# SCH_prosthetic_2026-05-21.net
KiCad netlist of a schematic drawn in EasyEDA
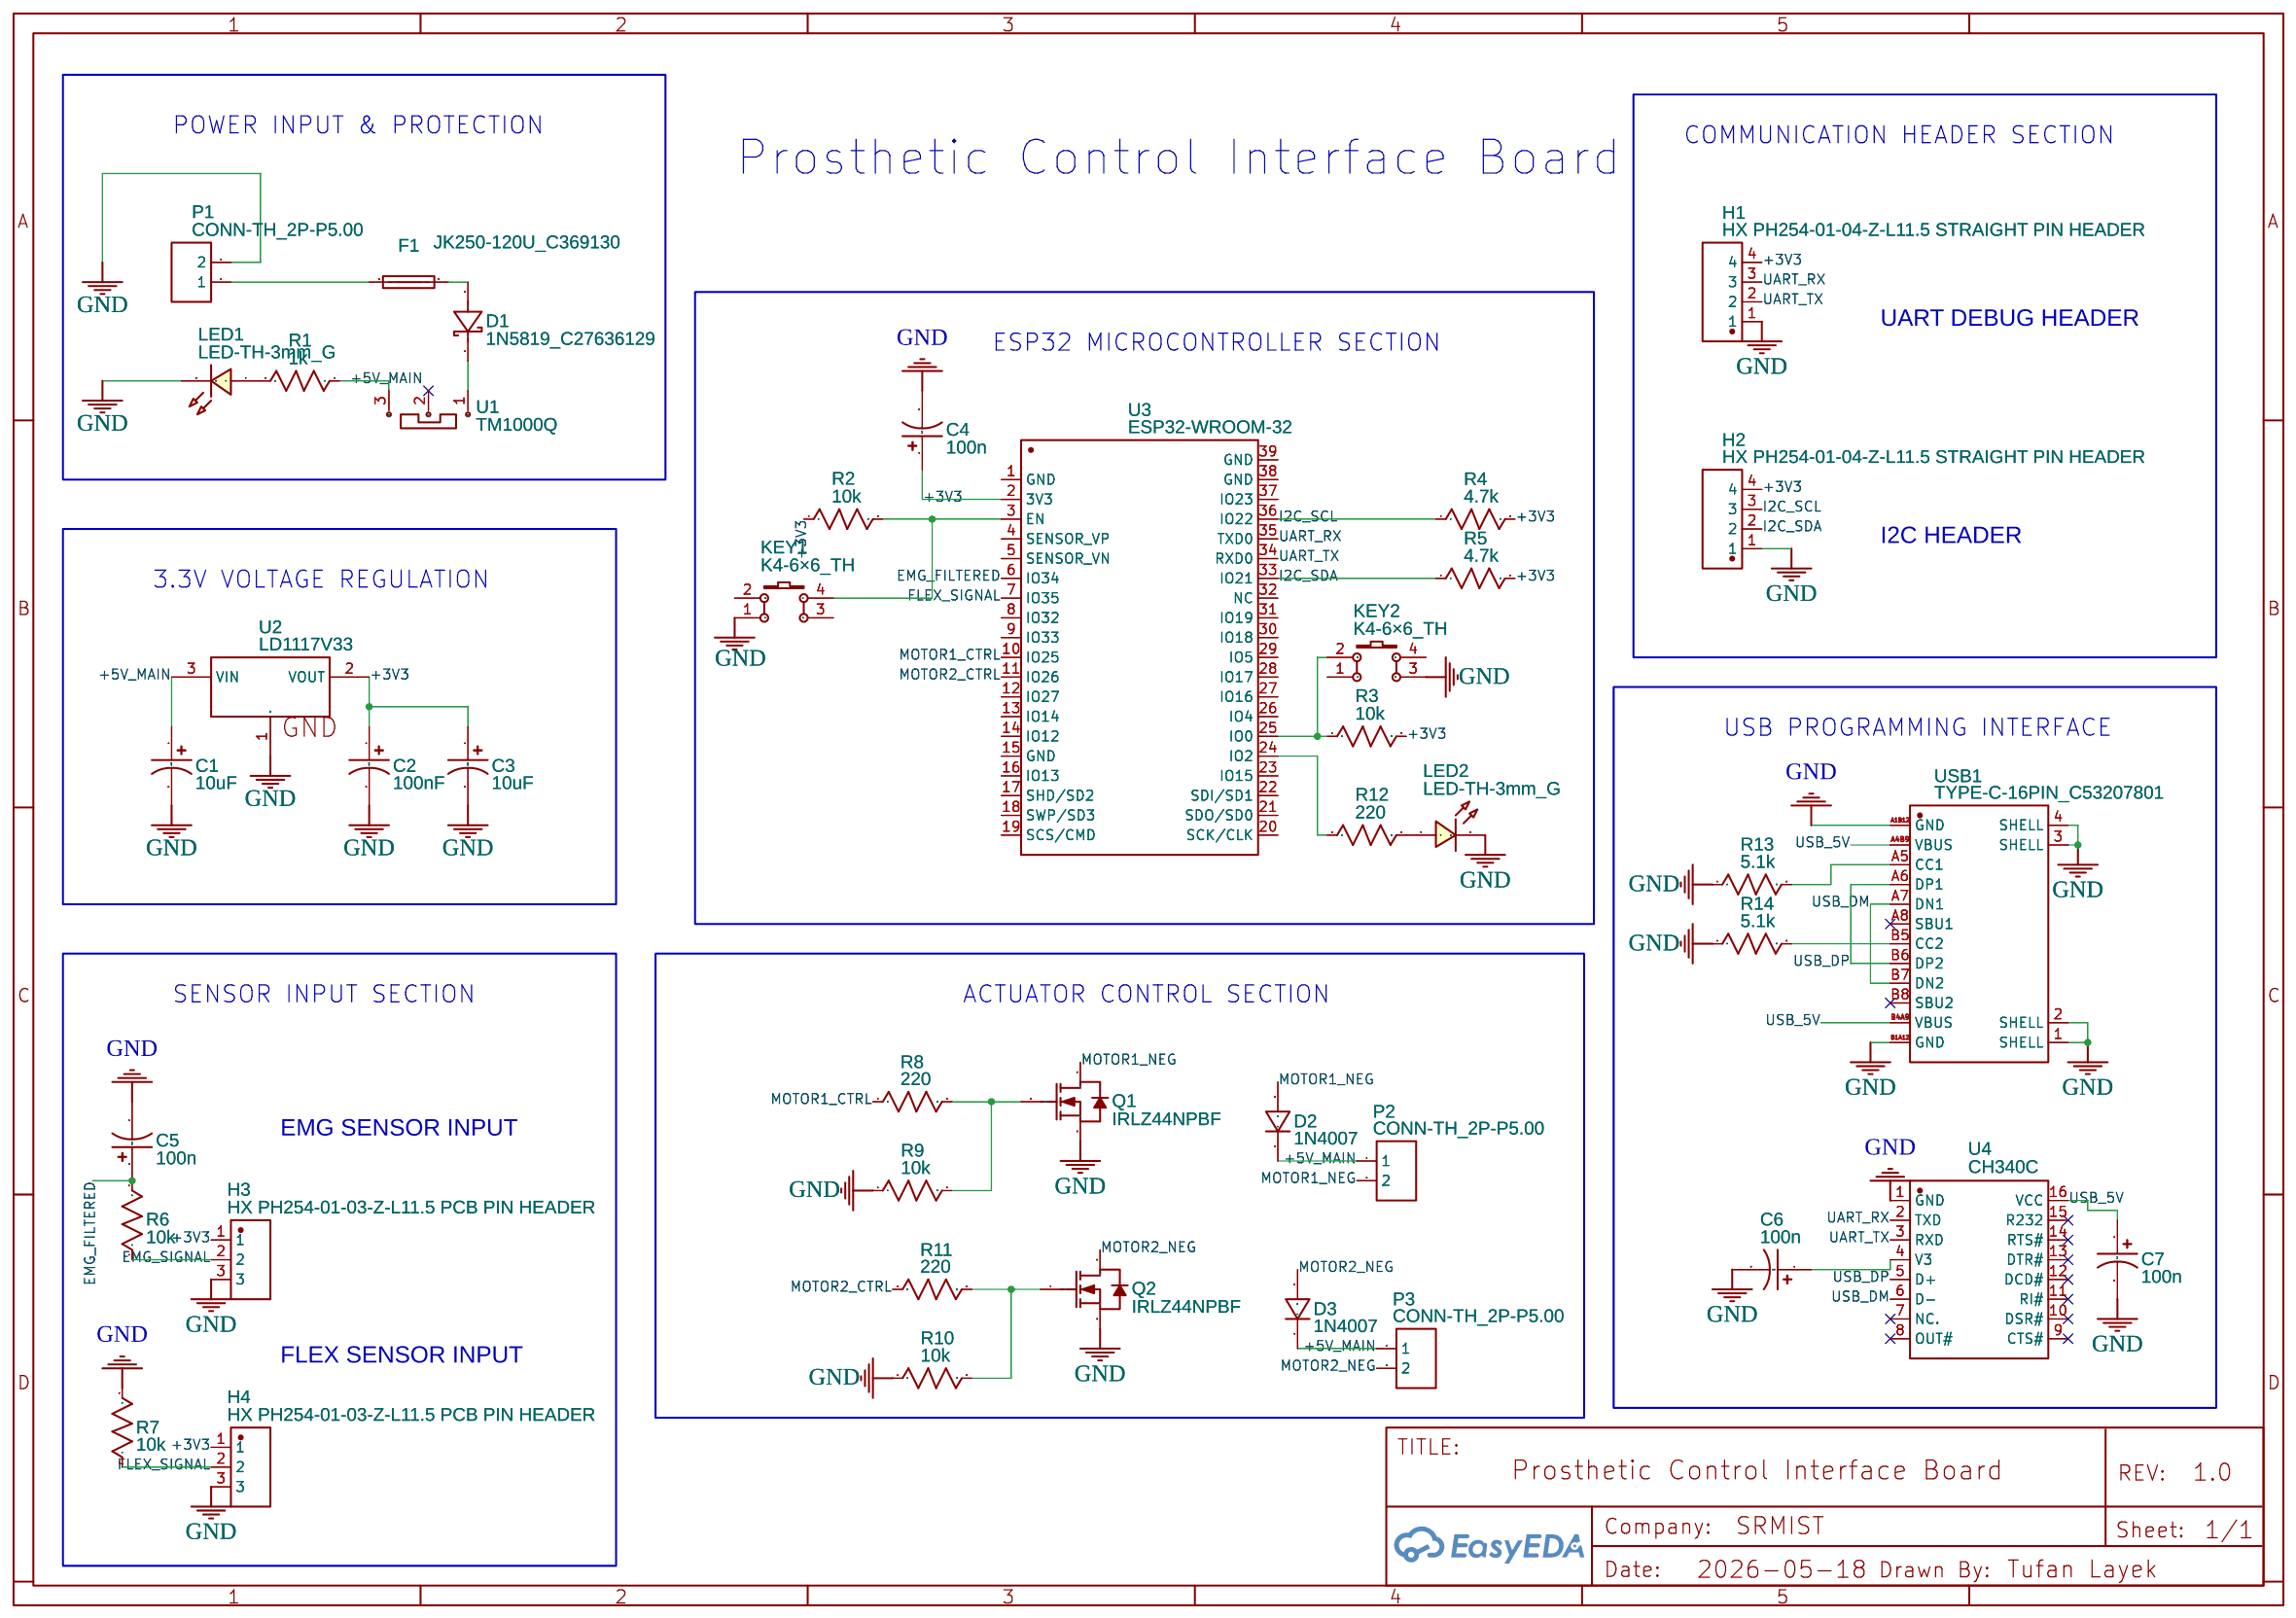
[diagram p0: schematic sheet]

(export (version "E")
  (design (tool "Eeschema 10.0.6"))
  (components
    (comp (ref "C1")
      (value "10uF")
      (fields (field (name "Manufacturer Part") "10UF50VC110GL") (field (name "Manufacturer") "Econd(米朗电子)"))
      (libsource (lib "") (part "CE_TH_D4.0×F1.5_US_2"))
    )
    (comp (ref "C2")
      (value "100nF")
      (fields
        (field (name "Manufacturer Part") "B220630V104J7ABLBY")
        (field (name "Manufacturer") "QIXING(七星)")
      )
      (libsource (lib "") (part "CE_TH_D4.0×F1.5_US_2"))
    )
    (comp (ref "C3")
      (value "10uF")
      (fields (field (name "Manufacturer Part") "10UF50VC110GL") (field (name "Manufacturer") "Econd(米朗电子)"))
      (libsource (lib "") (part "CE_TH_D4.0×F1.5_US_2"))
    )
    (comp (ref "C4")
      (value "100n")
      (fields (field (name "Manufacturer Part") "I104K44LEXLX") (field (name "Manufacturer") "CKX(錞谷)"))
      (libsource (lib "") (part "CE_TH_D4.0×F1.5_US_1"))
    )
    (comp (ref "C5")
      (value "100n")
      (fields (field (name "Manufacturer Part") "I104K44LEXLX") (field (name "Manufacturer") "CKX(錞谷)"))
      (libsource (lib "") (part "CE_TH_D4.0×F1.5_US_4"))
    )
    (comp (ref "C6")
      (value "100n")
      (fields (field (name "Manufacturer Part") "I104K44LEXLX") (field (name "Manufacturer") "CKX(錞谷)"))
      (libsource (lib "") (part "CE_TH_D4.0×F1.5_US"))
    )
    (comp (ref "C7")
      (value "100n")
      (fields (field (name "Manufacturer Part") "I104K44LEXLX") (field (name "Manufacturer") "CKX(錞谷)"))
      (libsource (lib "") (part "CE_TH_D4.0×F1.5_US_3"))
    )
    (comp (ref "D1")
      (value "1N5819_C27636129")
      (fields (field (name "Manufacturer Part") "1N5819") (field (name "Manufacturer") "DOWO(东沃)"))
      (libsource (lib "") (part "1N5819_C27636129"))
    )
    (comp (ref "D2")
      (value "1N4007")
      (fields (field (name "Manufacturer") "SEMTECH"))
      (libsource (lib "") (part "1N4007"))
    )
    (comp (ref "D3")
      (value "1N4007")
      (fields (field (name "Manufacturer") "SEMTECH"))
      (libsource (lib "") (part "1N4007"))
    )
    (comp (ref "F1")
      (value "JK250-120U_C369130")
      (fields (field (name "Manufacturer Part") "JK250-120U") (field (name "Manufacturer") "JK(金科)"))
      (libsource (lib "") (part "JK250-120U_C369130"))
    )
    (comp (ref "H1")
      (value "HX PH254-01-04-Z-L11.5 STRAIGHT PIN HEADER")
      (fields
        (field (name "Manufacturer Part") "HX PH254-01-04-Z-L11.5 straight pin header")
        (field (name "Manufacturer") "hanxia(韩下)")
      )
      (libsource (lib "") (part "HX PH254-01-04-Z-L11.5 STRAIGHT PIN HEADER"))
    )
    (comp (ref "H2")
      (value "HX PH254-01-04-Z-L11.5 STRAIGHT PIN HEADER")
      (fields
        (field (name "Manufacturer Part") "HX PH254-01-04-Z-L11.5 straight pin header")
        (field (name "Manufacturer") "hanxia(韩下)")
      )
      (libsource (lib "") (part "HX PH254-01-04-Z-L11.5 STRAIGHT PIN HEADER"))
    )
    (comp (ref "H3")
      (value "HX PH254-01-03-Z-L11.5 PCB PIN HEADER")
      (fields
        (field (name "Manufacturer Part") "HX PH254-01-03-Z-L11.5 pcb pin header")
        (field (name "Manufacturer") "hanxia(韩下)")
      )
      (libsource (lib "") (part "HX PH254-01-03-Z-L11.5 PCB PIN HEADER"))
    )
    (comp (ref "H4")
      (value "HX PH254-01-03-Z-L11.5 PCB PIN HEADER")
      (fields
        (field (name "Manufacturer Part") "HX PH254-01-03-Z-L11.5 pcb pin header")
        (field (name "Manufacturer") "hanxia(韩下)")
      )
      (libsource (lib "") (part "HX PH254-01-03-Z-L11.5 PCB PIN HEADER"))
    )
    (comp (ref "KEY1")
      (value "K4-6×6_TH")
      (fields (field (name "Manufacturer Part") "K2-1102DP-E4SW-04") (field (name "Manufacturer") "韩国韩荣"))
      (libsource (lib "") (part "K4-6×6_TH"))
    )
    (comp (ref "KEY2")
      (value "K4-6×6_TH")
      (fields (field (name "Manufacturer Part") "K2-1102DP-E4SW-04") (field (name "Manufacturer") "韩国韩荣"))
      (libsource (lib "") (part "K4-6×6_TH"))
    )
    (comp (ref "LED1")
      (value "LED-TH-3mm_G")
      (fields
        (field (name "Manufacturer Part") "204-10SYGD/S530-E3")
        (field (name "Manufacturer") "EVERLIGHT(台湾亿光)")
      )
      (libsource (lib "") (part "LED-TH-3mm_G_1"))
    )
    (comp (ref "LED2")
      (value "LED-TH-3mm_G")
      (fields
        (field (name "Manufacturer Part") "204-10SYGD/S530-E3")
        (field (name "Manufacturer") "EVERLIGHT(台湾亿光)")
      )
      (libsource (lib "") (part "LED-TH-3mm_G"))
    )
    (comp (ref "P1")
      (value "CONN-TH_2P-P5.00")
      (fields (field (name "Manufacturer Part") "KFM736D-5.0-2P") (field (name "Manufacturer") "KEFA(科发)"))
      (libsource (lib "") (part "CONN-TH_2P-P5.00"))
    )
    (comp (ref "P2")
      (value "CONN-TH_2P-P5.00")
      (fields (field (name "Manufacturer Part") "KFM736D-5.0-2P") (field (name "Manufacturer") "KEFA(科发)"))
      (libsource (lib "") (part "CONN-TH_2P-P5.00_1"))
    )
    (comp (ref "P3")
      (value "CONN-TH_2P-P5.00")
      (fields (field (name "Manufacturer Part") "KFM736D-5.0-2P") (field (name "Manufacturer") "KEFA(科发)"))
      (libsource (lib "") (part "CONN-TH_2P-P5.00_1"))
    )
    (comp (ref "Q1")
      (value "IRLZ44NPBF")
      (fields (field (name "Manufacturer") "Infineon(英飞凌)"))
      (libsource (lib "") (part "IRLZ44NPBF"))
    )
    (comp (ref "Q2")
      (value "IRLZ44NPBF")
      (fields (field (name "Manufacturer") "Infineon(英飞凌)"))
      (libsource (lib "") (part "IRLZ44NPBF"))
    )
    (comp (ref "R1")
      (value "1k")
      (fields (field (name "Manufacturer Part") "MFR-25FBF52-10K2") (field (name "Manufacturer") "YAGEO(国巨)"))
      (libsource (lib "") (part "R_AXIAL-0.3_US"))
    )
    (comp (ref "R2")
      (value "10k")
      (fields (field (name "Manufacturer Part") "MFR-25FBF52-10K2") (field (name "Manufacturer") "YAGEO(国巨)"))
      (libsource (lib "") (part "R_AXIAL-0.3_US_2"))
    )
    (comp (ref "R3")
      (value "10k")
      (fields (field (name "Manufacturer Part") "MFR-25FBF52-10K2") (field (name "Manufacturer") "YAGEO(国巨)"))
      (libsource (lib "") (part "R_AXIAL-0.3_US_2"))
    )
    (comp (ref "R4")
      (value "4.7k")
      (fields (field (name "Manufacturer Part") "OF472KE") (field (name "Manufacturer") "Ohmite"))
      (libsource (lib "") (part "R_AXIAL-0.3_US_2"))
    )
    (comp (ref "R5")
      (value "4.7k")
      (fields (field (name "Manufacturer Part") "OF472KE") (field (name "Manufacturer") "Ohmite"))
      (libsource (lib "") (part "R_AXIAL-0.3_US_2"))
    )
    (comp (ref "R6")
      (value "10k")
      (fields (field (name "Manufacturer Part") "MFR-25FBF52-10K2") (field (name "Manufacturer") "YAGEO(国巨)"))
      (libsource (lib "") (part "R_AXIAL-0.3_US_1"))
    )
    (comp (ref "R7")
      (value "10k")
      (fields (field (name "Manufacturer Part") "MFR-25FBF52-10K2") (field (name "Manufacturer") "YAGEO(国巨)"))
      (libsource (lib "") (part "R_AXIAL-0.3_US_1"))
    )
    (comp (ref "R8")
      (value "220")
      (fields (field (name "Manufacturer Part") "CR1/8W-220Ω±5%-ST52") (field (name "Manufacturer") "VO(翔胜)"))
      (libsource (lib "") (part "R_AXIAL-0.3_US_2"))
    )
    (comp (ref "R9")
      (value "10k")
      (fields (field (name "Manufacturer Part") "MFR-25FBF52-10K2") (field (name "Manufacturer") "YAGEO(国巨)"))
      (libsource (lib "") (part "R_AXIAL-0.3_US_2"))
    )
    (comp (ref "R10")
      (value "10k")
      (fields (field (name "Manufacturer Part") "MFR-25FBF52-10K2") (field (name "Manufacturer") "YAGEO(国巨)"))
      (libsource (lib "") (part "R_AXIAL-0.3_US_2"))
    )
    (comp (ref "R11")
      (value "220")
      (fields (field (name "Manufacturer Part") "CR1/8W-220Ω±5%-ST52") (field (name "Manufacturer") "VO(翔胜)"))
      (libsource (lib "") (part "R_AXIAL-0.3_US_2"))
    )
    (comp (ref "R12")
      (value "220")
      (fields (field (name "Manufacturer Part") "CR1/8W-220Ω±5%-ST52") (field (name "Manufacturer") "VO(翔胜)"))
      (libsource (lib "") (part "R_AXIAL-0.3_US_2"))
    )
    (comp (ref "R13")
      (value "5.1k")
      (fields (field (name "Manufacturer Part") "CR1/8W-5K1±5%-ST26") (field (name "Manufacturer") "VO(翔胜)"))
      (libsource (lib "") (part "R_AXIAL-0.3_US_2"))
    )
    (comp (ref "R14")
      (value "5.1k")
      (fields (field (name "Manufacturer Part") "CR1/8W-5K1±5%-ST26") (field (name "Manufacturer") "VO(翔胜)"))
      (libsource (lib "") (part "R_AXIAL-0.3_US_2"))
    )
    (comp (ref "U1")
      (value "TM1000Q")
      (fields (field (name "Manufacturer") "E-Switch"))
      (libsource (lib "") (part "TM1000Q"))
    )
    (comp (ref "U2")
      (value "LD1117V33")
      (fields (field (name "Manufacturer") "ST(意法半导体)"))
      (libsource (lib "") (part "LD1117V33"))
    )
    (comp (ref "U3")
      (value "ESP32-WROOM-32")
      (fields
        (field (name "Manufacturer Part") "ESP32-WROOM-32-N4")
        (field (name "Manufacturer") "ESPRESSIF(乐鑫)")
      )
      (libsource (lib "") (part "ESP32-WROOM-32"))
    )
    (comp (ref "U4")
      (value "CH340C")
      (fields (field (name "Manufacturer") "WCH(南京沁恒)"))
      (libsource (lib "") (part "CH340C"))
    )
    (comp (ref "USB1")
      (value "TYPE-C-16PIN_C53207801")
      (fields (field (name "Manufacturer Part") "TYPE-C-16PIN") (field (name "Manufacturer") "JXTCONN(聚兴泰)"))
      (libsource (lib "") (part "TYPE-C-16PIN_C53207801"))
    )
  )
  (nets
    (net (code "1") (name "/+3V3") (class "Default")
      (node (ref "C2") (pin "1") (pinfunction "1_1") (pintype "unspecified"))
      (node (ref "C3") (pin "1") (pinfunction "1_1") (pintype "unspecified"))
      (node (ref "C4") (pin "1") (pinfunction "1_1") (pintype "unspecified"))
      (node (ref "H1") (pin "4") (pinfunction "4_4") (pintype "unspecified"))
      (node (ref "H2") (pin "4") (pinfunction "4_4") (pintype "unspecified"))
      (node (ref "H3") (pin "1") (pinfunction "1_1") (pintype "unspecified"))
      (node (ref "H4") (pin "1") (pinfunction "1_1") (pintype "unspecified"))
      (node (ref "R2") (pin "1") (pinfunction "1_1") (pintype "unspecified"))
      (node (ref "R3") (pin "2") (pinfunction "2_2") (pintype "unspecified"))
      (node (ref "R4") (pin "2") (pinfunction "2_2") (pintype "unspecified"))
      (node (ref "R5") (pin "2") (pinfunction "2_2") (pintype "unspecified"))
      (node (ref "U2") (pin "2") (pinfunction "VOUT_2") (pintype "passive"))
      (node (ref "U3") (pin "2") (pinfunction "3V3_2") (pintype "unspecified"))
    )
    (net (code "2") (name "/+5V_MAIN") (class "Default")
      (node (ref "C1") (pin "1") (pinfunction "1_1") (pintype "unspecified"))
      (node (ref "D2") (pin "1") (pinfunction "1_1") (pintype "unspecified"))
      (node (ref "D3") (pin "1") (pinfunction "1_1") (pintype "unspecified"))
      (node (ref "P2") (pin "1") (pinfunction "1_1") (pintype "unspecified"))
      (node (ref "P3") (pin "1") (pinfunction "1_1") (pintype "unspecified"))
      (node (ref "R1") (pin "1") (pinfunction "1_1") (pintype "unspecified"))
      (node (ref "U1") (pin "3") (pinfunction "PIN3_3") (pintype "unspecified"))
      (node (ref "U2") (pin "3") (pinfunction "VIN_3") (pintype "passive"))
    )
    (net (code "3") (name "/EMG_FILTERED") (class "Default")
      (node (ref "C5") (pin "1") (pinfunction "1_1") (pintype "unspecified"))
      (node (ref "R6") (pin "2") (pinfunction "2_2") (pintype "unspecified"))
      (node (ref "U3") (pin "6") (pinfunction "IO34_6") (pintype "unspecified"))
    )
    (net (code "4") (name "/EMG_SIGNAL") (class "Default")
      (node (ref "H3") (pin "2") (pinfunction "2_2") (pintype "unspecified"))
      (node (ref "R6") (pin "1") (pinfunction "1_1") (pintype "unspecified"))
    )
    (net (code "5") (name "/FLEX_SIGNAL") (class "Default")
      (node (ref "H4") (pin "2") (pinfunction "2_2") (pintype "unspecified"))
      (node (ref "R7") (pin "1") (pinfunction "1_1") (pintype "unspecified"))
      (node (ref "U3") (pin "7") (pinfunction "IO35_7") (pintype "unspecified"))
    )
    (net (code "6") (name "/I2C_SCL") (class "Default")
      (node (ref "H2") (pin "3") (pinfunction "3_3") (pintype "unspecified"))
      (node (ref "R4") (pin "1") (pinfunction "1_1") (pintype "unspecified"))
      (node (ref "U3") (pin "36") (pinfunction "IO22_36") (pintype "unspecified"))
    )
    (net (code "7") (name "/I2C_SDA") (class "Default")
      (node (ref "H2") (pin "2") (pinfunction "2_2") (pintype "unspecified"))
      (node (ref "R5") (pin "1") (pinfunction "1_1") (pintype "unspecified"))
      (node (ref "U3") (pin "33") (pinfunction "IO21_33") (pintype "unspecified"))
    )
    (net (code "8") (name "/MOTOR1_CTRL") (class "Default")
      (node (ref "R8") (pin "1") (pinfunction "1_1") (pintype "unspecified"))
      (node (ref "U3") (pin "10") (pinfunction "IO25_10") (pintype "unspecified"))
    )
    (net (code "9") (name "/MOTOR1_NEG") (class "Default")
      (node (ref "D2") (pin "2") (pinfunction "2_2") (pintype "unspecified"))
      (node (ref "P2") (pin "2") (pinfunction "2_2") (pintype "unspecified"))
      (node (ref "Q1") (pin "2") (pinfunction "D_2") (pintype "unspecified"))
    )
    (net (code "10") (name "/MOTOR2_CTRL") (class "Default")
      (node (ref "R11") (pin "1") (pinfunction "1_1") (pintype "unspecified"))
      (node (ref "U3") (pin "11") (pinfunction "IO26_11") (pintype "unspecified"))
    )
    (net (code "11") (name "/MOTOR2_NEG") (class "Default")
      (node (ref "D3") (pin "2") (pinfunction "2_2") (pintype "unspecified"))
      (node (ref "P3") (pin "2") (pinfunction "2_2") (pintype "unspecified"))
      (node (ref "Q2") (pin "2") (pinfunction "D_2") (pintype "unspecified"))
    )
    (net (code "12") (name "/UART_RX") (class "Default")
      (node (ref "H1") (pin "3") (pinfunction "3_3") (pintype "unspecified"))
      (node (ref "U3") (pin "35") (pinfunction "TXD0_35") (pintype "unspecified"))
      (node (ref "U4") (pin "2") (pinfunction "TXD_2") (pintype "unspecified"))
    )
    (net (code "13") (name "/UART_TX") (class "Default")
      (node (ref "H1") (pin "2") (pinfunction "2_2") (pintype "unspecified"))
      (node (ref "U3") (pin "34") (pinfunction "RXD0_34") (pintype "unspecified"))
      (node (ref "U4") (pin "3") (pinfunction "RXD_3") (pintype "unspecified"))
    )
    (net (code "14") (name "/USB_5V") (class "Default")
      (node (ref "C7") (pin "1") (pinfunction "1_1") (pintype "unspecified"))
      (node (ref "U4") (pin "16") (pinfunction "VCC_16") (pintype "unspecified"))
      (node (ref "USB1") (pin "A4B9") (pinfunction "VBUS_A4B9") (pintype "unspecified"))
      (node (ref "USB1") (pin "B4A9") (pinfunction "VBUS_B4A9") (pintype "unspecified"))
    )
    (net (code "15") (name "/USB_DM") (class "Default")
      (node (ref "U4") (pin "6") (pinfunction "D-_6") (pintype "unspecified"))
      (node (ref "USB1") (pin "A7") (pinfunction "DN1_A7") (pintype "unspecified"))
      (node (ref "USB1") (pin "B7") (pinfunction "DN2_B7") (pintype "unspecified"))
    )
    (net (code "16") (name "/USB_DP") (class "Default")
      (node (ref "U4") (pin "5") (pinfunction "D+_5") (pintype "unspecified"))
      (node (ref "USB1") (pin "A6") (pinfunction "DP1_A6") (pintype "unspecified"))
      (node (ref "USB1") (pin "B6") (pinfunction "DP2_B6") (pintype "unspecified"))
    )
    (net (code "17") (name "GND") (class "Default")
      (node (ref "C1") (pin "2") (pinfunction "2_2") (pintype "unspecified"))
      (node (ref "C2") (pin "2") (pinfunction "2_2") (pintype "unspecified"))
      (node (ref "C3") (pin "2") (pinfunction "2_2") (pintype "unspecified"))
      (node (ref "C4") (pin "2") (pinfunction "2_2") (pintype "unspecified"))
      (node (ref "C5") (pin "2") (pinfunction "2_2") (pintype "unspecified"))
      (node (ref "C6") (pin "2") (pinfunction "2_2") (pintype "unspecified"))
      (node (ref "C7") (pin "2") (pinfunction "2_2") (pintype "unspecified"))
      (node (ref "H1") (pin "1") (pinfunction "1_1") (pintype "unspecified"))
      (node (ref "H2") (pin "1") (pinfunction "1_1") (pintype "unspecified"))
      (node (ref "H3") (pin "3") (pinfunction "3_3") (pintype "unspecified"))
      (node (ref "H4") (pin "3") (pinfunction "3_3") (pintype "unspecified"))
      (node (ref "KEY1") (pin "1") (pinfunction "1_1") (pintype "unspecified"))
      (node (ref "KEY2") (pin "3") (pinfunction "3_3") (pintype "unspecified"))
      (node (ref "LED1") (pin "2") (pinfunction "2_2") (pintype "unspecified"))
      (node (ref "LED2") (pin "2") (pinfunction "2_2") (pintype "unspecified"))
      (node (ref "P1") (pin "2") (pinfunction "2_2") (pintype "unspecified"))
      (node (ref "Q1") (pin "3") (pinfunction "S_3") (pintype "unspecified"))
      (node (ref "Q2") (pin "3") (pinfunction "S_3") (pintype "unspecified"))
      (node (ref "R10") (pin "1") (pinfunction "1_1") (pintype "unspecified"))
      (node (ref "R13") (pin "1") (pinfunction "1_1") (pintype "unspecified"))
      (node (ref "R14") (pin "1") (pinfunction "1_1") (pintype "unspecified"))
      (node (ref "R7") (pin "2") (pinfunction "2_2") (pintype "unspecified"))
      (node (ref "R9") (pin "1") (pinfunction "1_1") (pintype "unspecified"))
      (node (ref "U2") (pin "1") (pinfunction "GND_1") (pintype "unspecified"))
      (node (ref "U4") (pin "1") (pinfunction "GND_1") (pintype "unspecified"))
      (node (ref "USB1") (pin "1") (pinfunction "SHELL_1") (pintype "unspecified"))
      (node (ref "USB1") (pin "2") (pinfunction "SHELL_2") (pintype "unspecified"))
      (node (ref "USB1") (pin "3") (pinfunction "SHELL_3") (pintype "unspecified"))
      (node (ref "USB1") (pin "4") (pinfunction "SHELL_4") (pintype "unspecified"))
      (node (ref "USB1") (pin "A1B12") (pinfunction "GND_A1B12") (pintype "unspecified"))
      (node (ref "USB1") (pin "B1A12") (pinfunction "GND_B1A12") (pintype "unspecified"))
    )
    (net (code "18") (name "Net-(D1-A)") (class "Default")
      (node (ref "D1") (pin "2") (pinfunction "A_2") (pintype "unspecified"))
      (node (ref "F1") (pin "2") (pinfunction "2_2") (pintype "unspecified"))
    )
    (net (code "19") (name "Net-(D1-C)") (class "Default")
      (node (ref "D1") (pin "1") (pinfunction "C_1") (pintype "unspecified"))
      (node (ref "U1") (pin "1") (pinfunction "PIN1_1") (pintype "unspecified"))
    )
    (net (code "20") (name "Net-(F1-Pad1)") (class "Default")
      (node (ref "F1") (pin "1") (pinfunction "1_1") (pintype "unspecified"))
      (node (ref "P1") (pin "1") (pinfunction "1_1") (pintype "unspecified"))
    )
    (net (code "21") (name "Net-(LED1-Pad1)") (class "Default")
      (node (ref "LED1") (pin "1") (pinfunction "1_1") (pintype "unspecified"))
      (node (ref "R1") (pin "2") (pinfunction "2_2") (pintype "unspecified"))
    )
    (net (code "22") (name "Net-(LED2-Pad1)") (class "Default")
      (node (ref "LED2") (pin "1") (pinfunction "1_1") (pintype "unspecified"))
      (node (ref "R12") (pin "2") (pinfunction "2_2") (pintype "unspecified"))
    )
    (net (code "23") (name "Net-(Q1-G)") (class "Default")
      (node (ref "Q1") (pin "1") (pinfunction "G_1") (pintype "unspecified"))
      (node (ref "R8") (pin "2") (pinfunction "2_2") (pintype "unspecified"))
      (node (ref "R9") (pin "2") (pinfunction "2_2") (pintype "unspecified"))
    )
    (net (code "24") (name "Net-(Q2-G)") (class "Default")
      (node (ref "Q2") (pin "1") (pinfunction "G_1") (pintype "unspecified"))
      (node (ref "R10") (pin "2") (pinfunction "2_2") (pintype "unspecified"))
      (node (ref "R11") (pin "2") (pinfunction "2_2") (pintype "unspecified"))
    )
    (net (code "25") (name "Net-(U3-EN)") (class "Default")
      (node (ref "KEY1") (pin "4") (pinfunction "4_4") (pintype "unspecified"))
      (node (ref "R2") (pin "2") (pinfunction "2_2") (pintype "unspecified"))
      (node (ref "U3") (pin "3") (pinfunction "EN_3") (pintype "unspecified"))
    )
    (net (code "26") (name "Net-(U3-IO0)") (class "Default")
      (node (ref "KEY2") (pin "2") (pinfunction "2_2") (pintype "unspecified"))
      (node (ref "R3") (pin "1") (pinfunction "1_1") (pintype "unspecified"))
      (node (ref "U3") (pin "25") (pinfunction "IO0_25") (pintype "unspecified"))
    )
    (net (code "27") (name "Net-(U3-IO2)") (class "Default")
      (node (ref "R12") (pin "1") (pinfunction "1_1") (pintype "unspecified"))
      (node (ref "U3") (pin "24") (pinfunction "IO2_24") (pintype "unspecified"))
    )
    (net (code "28") (name "Net-(U4-V3)") (class "Default")
      (node (ref "C6") (pin "1") (pinfunction "1_1") (pintype "unspecified"))
      (node (ref "U4") (pin "4") (pinfunction "V3_4") (pintype "unspecified"))
    )
    (net (code "29") (name "Net-(USB1-CC1)") (class "Default")
      (node (ref "R13") (pin "2") (pinfunction "2_2") (pintype "unspecified"))
      (node (ref "USB1") (pin "A5") (pinfunction "CC1_A5") (pintype "unspecified"))
    )
    (net (code "30") (name "Net-(USB1-CC2)") (class "Default")
      (node (ref "R14") (pin "2") (pinfunction "2_2") (pintype "unspecified"))
      (node (ref "USB1") (pin "B5") (pinfunction "CC2_B5") (pintype "unspecified"))
    )
    (net (code "31") (name "unconnected-(KEY1-Pad2)") (class "Default")
      (node (ref "KEY1") (pin "2") (pinfunction "2_2") (pintype "unspecified"))
    )
    (net (code "32") (name "unconnected-(KEY1-Pad3)") (class "Default")
      (node (ref "KEY1") (pin "3") (pinfunction "3_3") (pintype "unspecified"))
    )
    (net (code "33") (name "unconnected-(KEY2-Pad1)") (class "Default")
      (node (ref "KEY2") (pin "1") (pinfunction "1_1") (pintype "unspecified"))
    )
    (net (code "34") (name "unconnected-(KEY2-Pad4)") (class "Default")
      (node (ref "KEY2") (pin "4") (pinfunction "4_4") (pintype "unspecified"))
    )
    (net (code "35") (name "unconnected-(U1-PIN2-Pad2)") (class "Default")
      (node (ref "U1") (pin "2") (pinfunction "PIN2_2") (pintype "unspecified+no_connect"))
    )
    (net (code "36") (name "unconnected-(U3-GND-Pad1)") (class "Default")
      (node (ref "U3") (pin "1") (pinfunction "GND_1") (pintype "unspecified"))
    )
    (net (code "37") (name "unconnected-(U3-GND-Pad15)") (class "Default")
      (node (ref "U3") (pin "15") (pinfunction "GND_15") (pintype "unspecified"))
    )
    (net (code "38") (name "unconnected-(U3-GND-Pad38)") (class "Default")
      (node (ref "U3") (pin "38") (pinfunction "GND_38") (pintype "unspecified"))
    )
    (net (code "39") (name "unconnected-(U3-GND-Pad39)") (class "Default")
      (node (ref "U3") (pin "39") (pinfunction "GND_39") (pintype "unspecified"))
    )
    (net (code "40") (name "unconnected-(U3-IO4-Pad26)") (class "Default")
      (node (ref "U3") (pin "26") (pinfunction "IO4_26") (pintype "unspecified"))
    )
    (net (code "41") (name "unconnected-(U3-IO5-Pad29)") (class "Default")
      (node (ref "U3") (pin "29") (pinfunction "IO5_29") (pintype "unspecified"))
    )
    (net (code "42") (name "unconnected-(U3-IO12-Pad14)") (class "Default")
      (node (ref "U3") (pin "14") (pinfunction "IO12_14") (pintype "unspecified"))
    )
    (net (code "43") (name "unconnected-(U3-IO13-Pad16)") (class "Default")
      (node (ref "U3") (pin "16") (pinfunction "IO13_16") (pintype "unspecified"))
    )
    (net (code "44") (name "unconnected-(U3-IO14-Pad13)") (class "Default")
      (node (ref "U3") (pin "13") (pinfunction "IO14_13") (pintype "unspecified"))
    )
    (net (code "45") (name "unconnected-(U3-IO15-Pad23)") (class "Default")
      (node (ref "U3") (pin "23") (pinfunction "IO15_23") (pintype "unspecified"))
    )
    (net (code "46") (name "unconnected-(U3-IO16-Pad27)") (class "Default")
      (node (ref "U3") (pin "27") (pinfunction "IO16_27") (pintype "unspecified"))
    )
    (net (code "47") (name "unconnected-(U3-IO17-Pad28)") (class "Default")
      (node (ref "U3") (pin "28") (pinfunction "IO17_28") (pintype "unspecified"))
    )
    (net (code "48") (name "unconnected-(U3-IO18-Pad30)") (class "Default")
      (node (ref "U3") (pin "30") (pinfunction "IO18_30") (pintype "unspecified"))
    )
    (net (code "49") (name "unconnected-(U3-IO19-Pad31)") (class "Default")
      (node (ref "U3") (pin "31") (pinfunction "IO19_31") (pintype "unspecified"))
    )
    (net (code "50") (name "unconnected-(U3-IO23-Pad37)") (class "Default")
      (node (ref "U3") (pin "37") (pinfunction "IO23_37") (pintype "unspecified"))
    )
    (net (code "51") (name "unconnected-(U3-IO27-Pad12)") (class "Default")
      (node (ref "U3") (pin "12") (pinfunction "IO27_12") (pintype "unspecified"))
    )
    (net (code "52") (name "unconnected-(U3-IO32-Pad8)") (class "Default")
      (node (ref "U3") (pin "8") (pinfunction "IO32_8") (pintype "unspecified"))
    )
    (net (code "53") (name "unconnected-(U3-IO33-Pad9)") (class "Default")
      (node (ref "U3") (pin "9") (pinfunction "IO33_9") (pintype "unspecified"))
    )
    (net (code "54") (name "unconnected-(U3-NC-Pad32)") (class "Default")
      (node (ref "U3") (pin "32") (pinfunction "NC_32") (pintype "unspecified"))
    )
    (net (code "55") (name "unconnected-(U3-SCK{slash}CLK-Pad20)") (class "Default")
      (node (ref "U3") (pin "20") (pinfunction "SCK/CLK_20") (pintype "unspecified"))
    )
    (net (code "56") (name "unconnected-(U3-SCS{slash}CMD-Pad19)") (class "Default")
      (node (ref "U3") (pin "19") (pinfunction "SCS/CMD_19") (pintype "unspecified"))
    )
    (net (code "57") (name "unconnected-(U3-SDI{slash}SD1-Pad22)") (class "Default")
      (node (ref "U3") (pin "22") (pinfunction "SDI/SD1_22") (pintype "unspecified"))
    )
    (net (code "58") (name "unconnected-(U3-SDO{slash}SD0-Pad21)") (class "Default")
      (node (ref "U3") (pin "21") (pinfunction "SDO/SD0_21") (pintype "unspecified"))
    )
    (net (code "59") (name "unconnected-(U3-SENSOR_VN-Pad5)") (class "Default")
      (node (ref "U3") (pin "5") (pinfunction "SENSOR_VN_5") (pintype "unspecified"))
    )
    (net (code "60") (name "unconnected-(U3-SENSOR_VP-Pad4)") (class "Default")
      (node (ref "U3") (pin "4") (pinfunction "SENSOR_VP_4") (pintype "unspecified"))
    )
    (net (code "61") (name "unconnected-(U3-SHD{slash}SD2-Pad17)") (class "Default")
      (node (ref "U3") (pin "17") (pinfunction "SHD/SD2_17") (pintype "unspecified"))
    )
    (net (code "62") (name "unconnected-(U3-SWP{slash}SD3-Pad18)") (class "Default")
      (node (ref "U3") (pin "18") (pinfunction "SWP/SD3_18") (pintype "unspecified"))
    )
    (net (code "63") (name "unconnected-(U4-CTS#-Pad9)") (class "Default")
      (node (ref "U4") (pin "9") (pinfunction "CTS#_9") (pintype "unspecified+no_connect"))
    )
    (net (code "64") (name "unconnected-(U4-DCD#-Pad12)") (class "Default")
      (node (ref "U4") (pin "12") (pinfunction "DCD#_12") (pintype "unspecified+no_connect"))
    )
    (net (code "65") (name "unconnected-(U4-DSR#-Pad10)") (class "Default")
      (node (ref "U4") (pin "10") (pinfunction "DSR#_10") (pintype "unspecified+no_connect"))
    )
    (net (code "66") (name "unconnected-(U4-DTR#-Pad13)") (class "Default")
      (node (ref "U4") (pin "13") (pinfunction "DTR#_13") (pintype "unspecified+no_connect"))
    )
    (net (code "67") (name "unconnected-(U4-NC.-Pad7)") (class "Default")
      (node (ref "U4") (pin "7") (pinfunction "NC._7") (pintype "unspecified+no_connect"))
    )
    (net (code "68") (name "unconnected-(U4-OUT#-Pad8)") (class "Default")
      (node (ref "U4") (pin "8") (pinfunction "OUT#_8") (pintype "unspecified+no_connect"))
    )
    (net (code "69") (name "unconnected-(U4-R232-Pad15)") (class "Default")
      (node (ref "U4") (pin "15") (pinfunction "R232_15") (pintype "unspecified+no_connect"))
    )
    (net (code "70") (name "unconnected-(U4-RI#-Pad11)") (class "Default")
      (node (ref "U4") (pin "11") (pinfunction "RI#_11") (pintype "unspecified+no_connect"))
    )
    (net (code "71") (name "unconnected-(U4-RTS#-Pad14)") (class "Default")
      (node (ref "U4") (pin "14") (pinfunction "RTS#_14") (pintype "unspecified+no_connect"))
    )
    (net (code "72") (name "unconnected-(USB1-SBU1-PadA8)") (class "Default")
      (node (ref "USB1") (pin "A8") (pinfunction "SBU1_A8") (pintype "unspecified+no_connect"))
    )
    (net (code "73") (name "unconnected-(USB1-SBU2-PadB8)") (class "Default")
      (node (ref "USB1") (pin "B8") (pinfunction "SBU2_B8") (pintype "unspecified+no_connect"))
    )
  )
)
